# SOIC16.net
KiCad netlist of a schematic drawn in Altium Designer
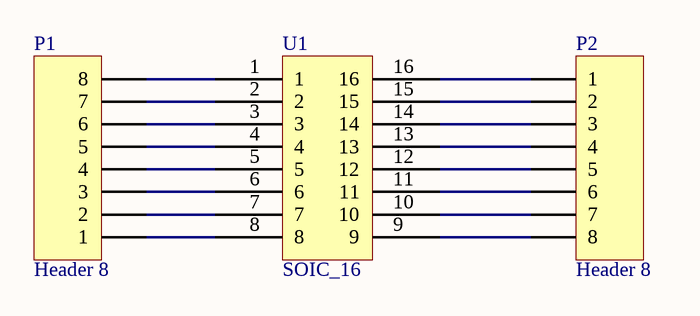
[diagram p0: SOIC16.SchDoc]

(export (version "E")
  (design (tool "Eeschema 10.0.6"))
  (components
    (comp (ref "P1")
      (value "Header 8")
      (footprint "HDR1X8")
      (description "Header, 8-Pin")
      (fields (field (name "PUBLISHER") "Altium Limited"))
      (libsource (lib "Miscellaneous Connectors") (part "Header 8"))
    )
    (comp (ref "P2")
      (value "Header 8")
      (footprint "HDR1X8")
      (description "Header, 8-Pin")
      (fields (field (name "PUBLISHER") "Altium Limited"))
      (libsource (lib "") (part "Header 8_1"))
    )
    (comp (ref "U1")
      (value "SOIC_16")
      (footprint "SOIC16")
      (libsource (lib "PCB_Breakout_Boards") (part "SOIC_16"))
    )
  )
  (nets
    (net (code "1") (name "Net-(P1-Pad1)") (class "Default")
      (node (ref "P1") (pin "1") (pinfunction "1_1") (pintype "passive"))
      (node (ref "U1") (pin "8") (pinfunction "8_8") (pintype "passive"))
    )
    (net (code "2") (name "Net-(P1-Pad2)") (class "Default")
      (node (ref "P1") (pin "2") (pinfunction "2_2") (pintype "passive"))
      (node (ref "U1") (pin "7") (pinfunction "7_7") (pintype "passive"))
    )
    (net (code "3") (name "Net-(P1-Pad3)") (class "Default")
      (node (ref "P1") (pin "3") (pinfunction "3_3") (pintype "passive"))
      (node (ref "U1") (pin "6") (pinfunction "6_6") (pintype "passive"))
    )
    (net (code "4") (name "Net-(P1-Pad4)") (class "Default")
      (node (ref "P1") (pin "4") (pinfunction "4_4") (pintype "passive"))
      (node (ref "U1") (pin "5") (pinfunction "5_5") (pintype "passive"))
    )
    (net (code "5") (name "Net-(P1-Pad5)") (class "Default")
      (node (ref "P1") (pin "5") (pinfunction "5_5") (pintype "passive"))
      (node (ref "U1") (pin "4") (pinfunction "4_4") (pintype "passive"))
    )
    (net (code "6") (name "Net-(P1-Pad6)") (class "Default")
      (node (ref "P1") (pin "6") (pinfunction "6_6") (pintype "passive"))
      (node (ref "U1") (pin "3") (pinfunction "3_3") (pintype "passive"))
    )
    (net (code "7") (name "Net-(P1-Pad7)") (class "Default")
      (node (ref "P1") (pin "7") (pinfunction "7_7") (pintype "passive"))
      (node (ref "U1") (pin "2") (pinfunction "2_2") (pintype "passive"))
    )
    (net (code "8") (name "Net-(P1-Pad8)") (class "Default")
      (node (ref "P1") (pin "8") (pinfunction "8_8") (pintype "passive"))
      (node (ref "U1") (pin "1") (pinfunction "1_1") (pintype "passive"))
    )
    (net (code "9") (name "Net-(P2-Pad1)") (class "Default")
      (node (ref "P2") (pin "1") (pinfunction "1_1") (pintype "passive"))
      (node (ref "U1") (pin "16") (pinfunction "16_16") (pintype "passive"))
    )
    (net (code "10") (name "Net-(P2-Pad2)") (class "Default")
      (node (ref "P2") (pin "2") (pinfunction "2_2") (pintype "passive"))
      (node (ref "U1") (pin "15") (pinfunction "15_15") (pintype "passive"))
    )
    (net (code "11") (name "Net-(P2-Pad3)") (class "Default")
      (node (ref "P2") (pin "3") (pinfunction "3_3") (pintype "passive"))
      (node (ref "U1") (pin "14") (pinfunction "14_14") (pintype "passive"))
    )
    (net (code "12") (name "Net-(P2-Pad4)") (class "Default")
      (node (ref "P2") (pin "4") (pinfunction "4_4") (pintype "passive"))
      (node (ref "U1") (pin "13") (pinfunction "13_13") (pintype "passive"))
    )
    (net (code "13") (name "Net-(P2-Pad5)") (class "Default")
      (node (ref "P2") (pin "5") (pinfunction "5_5") (pintype "passive"))
      (node (ref "U1") (pin "12") (pinfunction "12_12") (pintype "passive"))
    )
    (net (code "14") (name "Net-(P2-Pad6)") (class "Default")
      (node (ref "P2") (pin "6") (pinfunction "6_6") (pintype "passive"))
      (node (ref "U1") (pin "11") (pinfunction "11_11") (pintype "passive"))
    )
    (net (code "15") (name "Net-(P2-Pad7)") (class "Default")
      (node (ref "P2") (pin "7") (pinfunction "7_7") (pintype "passive"))
      (node (ref "U1") (pin "10") (pinfunction "10_10") (pintype "passive"))
    )
    (net (code "16") (name "Net-(P2-Pad8)") (class "Default")
      (node (ref "P2") (pin "8") (pinfunction "8_8") (pintype "passive"))
      (node (ref "U1") (pin "9") (pinfunction "9_9") (pintype "passive"))
    )
  )
)
